# ST_Link.net
KiCad netlist of a schematic drawn in Altium Designer
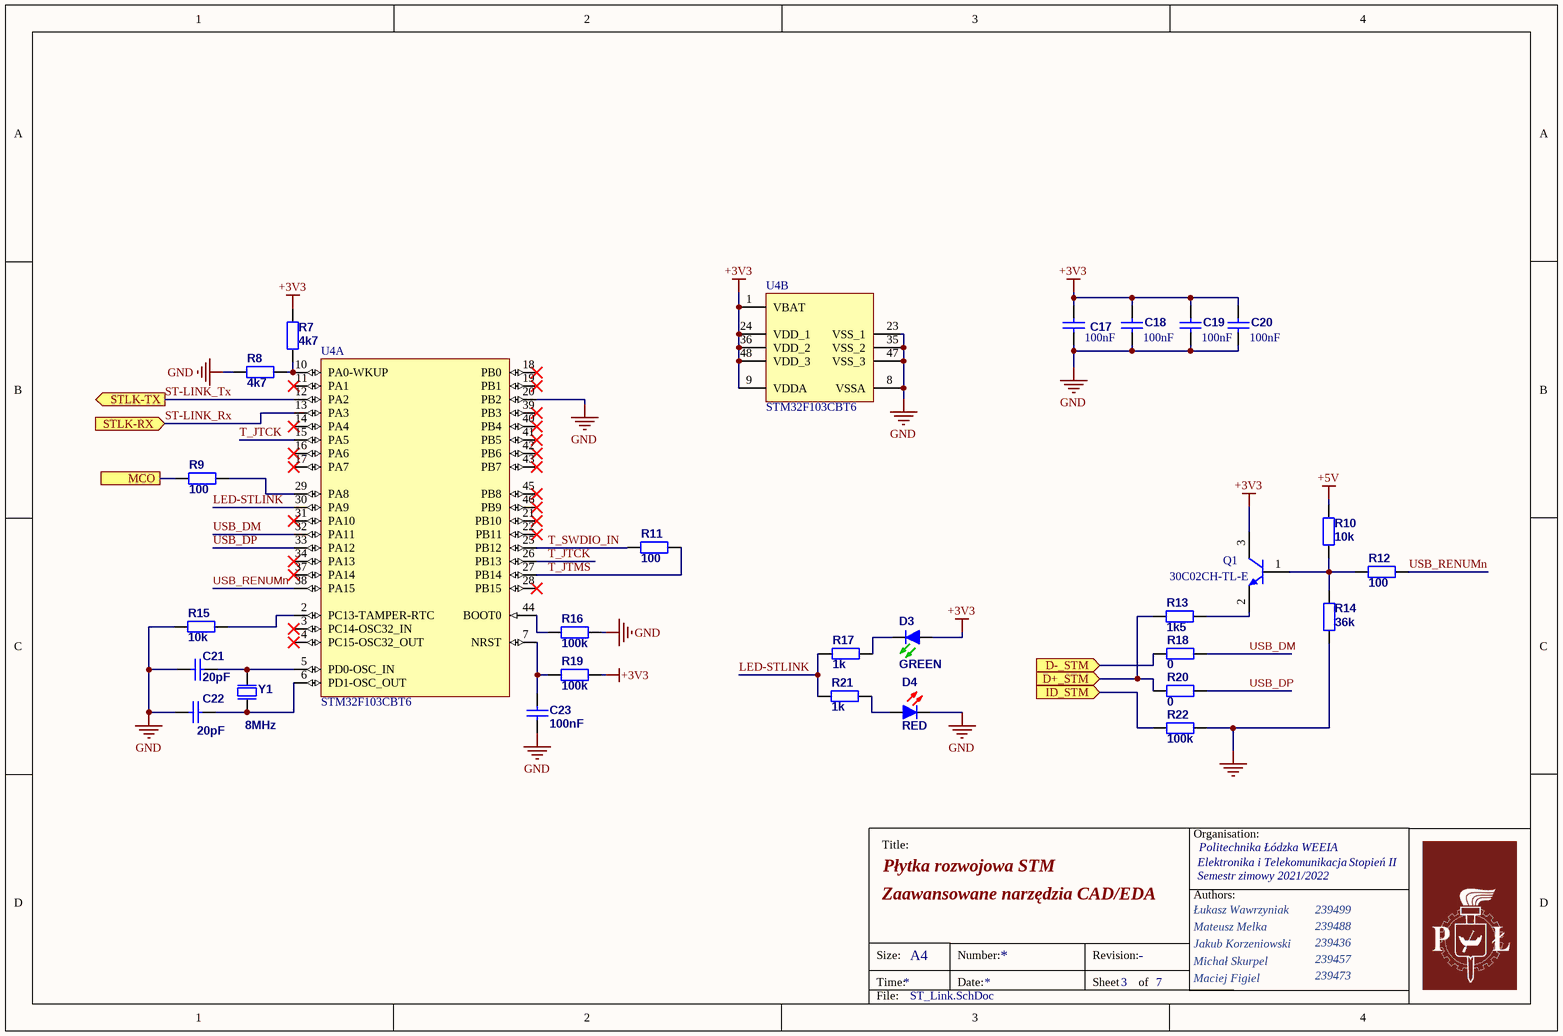
[diagram p0: ST_Link.SchDoc]

(export (version "E")
  (design (tool "Eeschema 10.0.6"))
  (components
    (comp (ref "C17")
      (value "100nF")
      (footprint "PCB1:0805")
      (description "Ceramic capacitor MLCC SMD ±1%")
      (libsource (lib "capacitors") (part "Cap"))
    )
    (comp (ref "C18")
      (value "100nF")
      (footprint "PCB1:0805")
      (description "Ceramic capacitor MLCC SMD ±1%")
      (libsource (lib "capacitors") (part "Cap"))
    )
    (comp (ref "C19")
      (value "100nF")
      (footprint "PCB1:0805")
      (description "Ceramic capacitor MLCC SMD ±1%")
      (libsource (lib "capacitors") (part "Cap"))
    )
    (comp (ref "C20")
      (value "100nF")
      (footprint "PCB1:0805")
      (description "Ceramic capacitor MLCC SMD ±1%")
      (libsource (lib "capacitors") (part "Cap"))
    )
    (comp (ref "C21")
      (value "20pF")
      (footprint "PCB1:0805")
      (description "Ceramic capacitor MLCC SMD ±1%")
      (libsource (lib "capacitors") (part "Cap"))
    )
    (comp (ref "C22")
      (value "20pF")
      (footprint "PCB1:0805")
      (description "Ceramic capacitor MLCC SMD ±1%")
      (libsource (lib "capacitors") (part "Cap"))
    )
    (comp (ref "C23")
      (value "100nF")
      (footprint "PCB1:0805")
      (description "Ceramic capacitor MLCC SMD ±5%")
      (libsource (lib "capacitors") (part "Cap"))
    )
    (comp (ref "D3")
      (value "GREEN")
      (footprint "LED1206G")
      (description "GREEN LED")
      (libsource (lib "leds") (part "LED_GREEN"))
    )
    (comp (ref "D4")
      (value "RED")
      (footprint "LED1206R")
      (description "RED LED")
      (libsource (lib "leds") (part "LED_RED"))
    )
    (comp (ref "Q1")
      (value "30C02CH-TL-E")
      (footprint "ONSC-CPH-3_V")
      (description "Bipolar Transistor,, Low VCE(sat), NPN Single, 3-Pin CPH, Pb-Free, Tape and Reel")
      (fields (field (name "MANUFACTURER") "On Semiconductor") (field (name "VOLTAGE") "30 V"))
      (libsource (lib "Altium Content Vault") (part "ONSC-30C02CH-CPH-3-318BA"))
    )
    (comp (ref "R7")
      (value "4k7")
      (footprint "PCB1:0805")
      (description "Resistor SMD  ±5%")
      (libsource (lib "resistors") (part "Res"))
    )
    (comp (ref "R8")
      (value "4k7")
      (footprint "PCB1:0805")
      (description "Resistor SMD  ±5%")
      (libsource (lib "") (part "Res_1"))
    )
    (comp (ref "R9")
      (value "100")
      (footprint "PCB1:0805")
      (description "Resistor SMD  ±5%")
      (libsource (lib "") (part "Res_1"))
    )
    (comp (ref "R10")
      (value "10k")
      (footprint "PCB1:0805")
      (description "Resistor SMD  ±5%")
      (libsource (lib "") (part "Res_2"))
    )
    (comp (ref "R11")
      (value "100")
      (footprint "PCB1:0805")
      (description "Resistor SMD  ±5%")
      (libsource (lib "") (part "Res_1"))
    )
    (comp (ref "R12")
      (value "100")
      (footprint "PCB1:0805")
      (description "Resistor SMD  ±5%")
      (libsource (lib "") (part "Res_3"))
    )
    (comp (ref "R13")
      (value "1k5")
      (footprint "PCB1:0805")
      (description "Resistor SMD  ±5%")
      (libsource (lib "") (part "Res_1"))
    )
    (comp (ref "R14")
      (value "36k")
      (footprint "PCB1:0805")
      (description "Resistor SMD  ±5%")
      (libsource (lib "resistors") (part "Res"))
    )
    (comp (ref "R15")
      (value "10k")
      (footprint "PCB1:0805")
      (description "Resistor SMD  ±5%")
      (libsource (lib "") (part "Res_1"))
    )
    (comp (ref "R16")
      (value "100k")
      (footprint "PCB1:0805")
      (description "Resistor SMD  ±5%")
      (libsource (lib "") (part "Res_1"))
    )
    (comp (ref "R17")
      (value "1k")
      (footprint "PCB1:0805")
      (description "Resistor SMD  ±5%")
      (libsource (lib "") (part "Res_1"))
    )
    (comp (ref "R18")
      (value "0")
      (footprint "PCB1:0805")
      (description "Resistor SMD  ±5%")
      (libsource (lib "") (part "Res_1"))
    )
    (comp (ref "R19")
      (value "100k")
      (footprint "PCB1:0805")
      (description "Resistor SMD  ±5%")
      (libsource (lib "") (part "Res_1"))
    )
    (comp (ref "R20")
      (value "0")
      (footprint "PCB1:0805")
      (description "Resistor SMD  ±5%")
      (libsource (lib "") (part "Res_1"))
    )
    (comp (ref "R21")
      (value "1k")
      (footprint "PCB1:0805")
      (description "Resistor SMD  ±5%")
      (libsource (lib "") (part "Res_1"))
    )
    (comp (ref "R22")
      (value "100k")
      (footprint "PCB1:0805")
      (description "Resistor SMD  ±5%")
      (libsource (lib "") (part "Res_1"))
    )
    (comp (ref "U4")
      (value "STM32F103CBT6")
      (footprint "STM-LQFP48_L")
      (fields (field (name "VOLTAGE") "3.3V"))
      (libsource (lib "Altium Content Vault") (part "MC-ARM-STM32F103X8_B-SQ48"))
    )
    (comp (ref "Y1")
      (value "8MHz")
      (footprint "HC49/4H")
      (description "Crystal Oscillator (20pF)")
      (libsource (lib "quartz_crystals_and_filters") (part "XTAL_2PIN"))
    )
  )
  (nets
    (net (code "1") (name "+3V3") (class "Default")
      (node (ref "C17") (pin "2") (pinfunction "2_2") (pintype "passive"))
      (node (ref "C18") (pin "2") (pinfunction "2_2") (pintype "passive"))
      (node (ref "C19") (pin "2") (pinfunction "2_2") (pintype "passive"))
      (node (ref "C20") (pin "2") (pinfunction "2_2") (pintype "passive"))
      (node (ref "D3") (pin "1") (pinfunction "A_1") (pintype "passive"))
      (node (ref "Q1") (pin "3") (pinfunction "C_3") (pintype "passive"))
      (node (ref "R19") (pin "1") (pinfunction "1_1") (pintype "passive"))
      (node (ref "R7") (pin "1") (pinfunction "1_1") (pintype "passive"))
      (node (ref "U4") (pin "1") (pinfunction "VBAT_1") (pintype "power_in"))
      (node (ref "U4") (pin "24") (pinfunction "VDD_1_24") (pintype "power_in"))
      (node (ref "U4") (pin "36") (pinfunction "VDD_2_36") (pintype "power_in"))
      (node (ref "U4") (pin "48") (pinfunction "VDD_3_48") (pintype "power_in"))
      (node (ref "U4") (pin "9") (pinfunction "VDDA_9") (pintype "power_in"))
    )
    (net (code "2") (name "+5V") (class "Default")
      (node (ref "R10") (pin "2") (pinfunction "2_2") (pintype "passive"))
    )
    (net (code "3") (name "/D+_STM") (class "Default")
      (node (ref "R13") (pin "2") (pinfunction "2_2") (pintype "passive"))
      (node (ref "R20") (pin "2") (pinfunction "2_2") (pintype "passive"))
    )
    (net (code "4") (name "/D-_STM") (class "Default")
      (node (ref "R18") (pin "2") (pinfunction "2_2") (pintype "passive"))
    )
    (net (code "5") (name "/ID_STM") (class "Default")
      (node (ref "R22") (pin "2") (pinfunction "2_2") (pintype "passive"))
    )
    (net (code "6") (name "/LED-STLINK") (class "Default")
      (node (ref "R17") (pin "2") (pinfunction "2_2") (pintype "passive"))
      (node (ref "R21") (pin "2") (pinfunction "2_2") (pintype "passive"))
      (node (ref "U4") (pin "30") (pinfunction "PA9_30") (pintype "bidirectional"))
    )
    (net (code "7") (name "/MCO") (class "Default")
      (node (ref "R9") (pin "2") (pinfunction "2_2") (pintype "passive"))
    )
    (net (code "8") (name "/ST-LINK_Rx") (class "Default")
      (node (ref "U4") (pin "13") (pinfunction "PA3_13") (pintype "bidirectional"))
    )
    (net (code "9") (name "/ST-LINK_Tx") (class "Default")
      (node (ref "U4") (pin "12") (pinfunction "PA2_12") (pintype "bidirectional"))
    )
    (net (code "10") (name "/T_JTCK") (class "Default")
      (node (ref "U4") (pin "15") (pinfunction "PA5_15") (pintype "bidirectional"))
      (node (ref "U4") (pin "26") (pinfunction "PB13_26") (pintype "bidirectional"))
    )
    (net (code "11") (name "/T_JTMS") (class "Default")
      (node (ref "R11") (pin "1") (pinfunction "1_1") (pintype "passive"))
      (node (ref "U4") (pin "27") (pinfunction "PB14_27") (pintype "bidirectional"))
    )
    (net (code "12") (name "/T_SWDIO_IN") (class "Default")
      (node (ref "R11") (pin "2") (pinfunction "2_2") (pintype "passive"))
      (node (ref "U4") (pin "25") (pinfunction "PB12_25") (pintype "bidirectional"))
    )
    (net (code "13") (name "/USB_DM") (class "Default")
      (node (ref "R18") (pin "1") (pinfunction "1_1") (pintype "passive"))
      (node (ref "U4") (pin "32") (pinfunction "PA11_32") (pintype "bidirectional"))
    )
    (net (code "14") (name "/USB_DP") (class "Default")
      (node (ref "R20") (pin "1") (pinfunction "1_1") (pintype "passive"))
      (node (ref "U4") (pin "33") (pinfunction "PA12_33") (pintype "bidirectional"))
    )
    (net (code "15") (name "/USB_RENUMn") (class "Default")
      (node (ref "R12") (pin "2") (pinfunction "2_2") (pintype "passive"))
      (node (ref "U4") (pin "38") (pinfunction "PA15_38") (pintype "bidirectional"))
    )
    (net (code "16") (name "GND") (class "Default")
      (node (ref "C17") (pin "1") (pinfunction "1_1") (pintype "passive"))
      (node (ref "C18") (pin "1") (pinfunction "1_1") (pintype "passive"))
      (node (ref "C19") (pin "1") (pinfunction "1_1") (pintype "passive"))
      (node (ref "C20") (pin "1") (pinfunction "1_1") (pintype "passive"))
      (node (ref "C21") (pin "1") (pinfunction "1_1") (pintype "passive"))
      (node (ref "C22") (pin "1") (pinfunction "1_1") (pintype "passive"))
      (node (ref "C23") (pin "1") (pinfunction "1_1") (pintype "passive"))
      (node (ref "D4") (pin "2") (pinfunction "K_2") (pintype "passive"))
      (node (ref "R14") (pin "2") (pinfunction "2_2") (pintype "passive"))
      (node (ref "R15") (pin "2") (pinfunction "2_2") (pintype "passive"))
      (node (ref "R16") (pin "1") (pinfunction "1_1") (pintype "passive"))
      (node (ref "R22") (pin "1") (pinfunction "1_1") (pintype "passive"))
      (node (ref "R8") (pin "2") (pinfunction "2_2") (pintype "passive"))
      (node (ref "U4") (pin "20") (pinfunction "PB2_20") (pintype "bidirectional"))
      (node (ref "U4") (pin "23") (pinfunction "VSS_1_23") (pintype "power_in"))
      (node (ref "U4") (pin "35") (pinfunction "VSS_2_35") (pintype "power_in"))
      (node (ref "U4") (pin "47") (pinfunction "VSS_3_47") (pintype "power_in"))
      (node (ref "U4") (pin "8") (pinfunction "VSSA_8") (pintype "power_in"))
    )
    (net (code "17") (name "Net-(D3-K)") (class "Default")
      (node (ref "D3") (pin "2") (pinfunction "K_2") (pintype "passive"))
      (node (ref "R17") (pin "1") (pinfunction "1_1") (pintype "passive"))
    )
    (net (code "18") (name "Net-(D4-A)") (class "Default")
      (node (ref "D4") (pin "1") (pinfunction "A_1") (pintype "passive"))
      (node (ref "R21") (pin "1") (pinfunction "1_1") (pintype "passive"))
    )
    (net (code "19") (name "Net-(Q1-B)") (class "Default")
      (node (ref "Q1") (pin "1") (pinfunction "B_1") (pintype "passive"))
      (node (ref "R10") (pin "1") (pinfunction "1_1") (pintype "passive"))
      (node (ref "R12") (pin "1") (pinfunction "1_1") (pintype "passive"))
      (node (ref "R14") (pin "1") (pinfunction "1_1") (pintype "passive"))
    )
    (net (code "20") (name "Net-(Q1-E)") (class "Default")
      (node (ref "Q1") (pin "2") (pinfunction "E_2") (pintype "passive"))
      (node (ref "R13") (pin "1") (pinfunction "1_1") (pintype "passive"))
    )
    (net (code "21") (name "Net-(U4A-BOOT0)") (class "Default")
      (node (ref "R16") (pin "2") (pinfunction "2_2") (pintype "passive"))
      (node (ref "U4") (pin "44") (pinfunction "BOOT0_44") (pintype "input"))
    )
    (net (code "22") (name "Net-(U4A-NRST)") (class "Default")
      (node (ref "C23") (pin "2") (pinfunction "2_2") (pintype "passive"))
      (node (ref "R19") (pin "2") (pinfunction "2_2") (pintype "passive"))
      (node (ref "U4") (pin "7") (pinfunction "NRST_7") (pintype "bidirectional"))
    )
    (net (code "23") (name "Net-(U4A-PA0-WKUP)") (class "Default")
      (node (ref "R7") (pin "2") (pinfunction "2_2") (pintype "passive"))
      (node (ref "R8") (pin "1") (pinfunction "1_1") (pintype "passive"))
      (node (ref "U4") (pin "10") (pinfunction "PA0-WKUP_10") (pintype "bidirectional"))
    )
    (net (code "24") (name "Net-(U4A-PA8)") (class "Default")
      (node (ref "R9") (pin "1") (pinfunction "1_1") (pintype "passive"))
      (node (ref "U4") (pin "29") (pinfunction "PA8_29") (pintype "bidirectional"))
    )
    (net (code "25") (name "Net-(U4A-PC13-TAMPER-RTC)") (class "Default")
      (node (ref "R15") (pin "1") (pinfunction "1_1") (pintype "passive"))
      (node (ref "U4") (pin "2") (pinfunction "PC13-TAMPER-RTC_2") (pintype "bidirectional"))
    )
    (net (code "26") (name "Net-(U4A-PD0-OSC_IN)") (class "Default")
      (node (ref "C21") (pin "2") (pinfunction "2_2") (pintype "passive"))
      (node (ref "U4") (pin "5") (pinfunction "PD0-OSC_IN_5") (pintype "bidirectional"))
      (node (ref "Y1") (pin "2") (pinfunction "OSC2_2") (pintype "passive"))
    )
    (net (code "27") (name "Net-(U4A-PD1-OSC_OUT)") (class "Default")
      (node (ref "C22") (pin "2") (pinfunction "2_2") (pintype "passive"))
      (node (ref "U4") (pin "6") (pinfunction "PD1-OSC_OUT_6") (pintype "bidirectional"))
      (node (ref "Y1") (pin "1") (pinfunction "OSC1_1") (pintype "passive"))
    )
    (net (code "28") (name "unconnected-(U4A-PA1-Pad11)") (class "Default")
      (node (ref "U4") (pin "11") (pinfunction "PA1_11") (pintype "bidirectional+no_connect"))
    )
    (net (code "29") (name "unconnected-(U4A-PA4-Pad14)") (class "Default")
      (node (ref "U4") (pin "14") (pinfunction "PA4_14") (pintype "bidirectional+no_connect"))
    )
    (net (code "30") (name "unconnected-(U4A-PA6-Pad16)") (class "Default")
      (node (ref "U4") (pin "16") (pinfunction "PA6_16") (pintype "bidirectional+no_connect"))
    )
    (net (code "31") (name "unconnected-(U4A-PA7-Pad17)") (class "Default")
      (node (ref "U4") (pin "17") (pinfunction "PA7_17") (pintype "bidirectional+no_connect"))
    )
    (net (code "32") (name "unconnected-(U4A-PA10-Pad31)") (class "Default")
      (node (ref "U4") (pin "31") (pinfunction "PA10_31") (pintype "bidirectional+no_connect"))
    )
    (net (code "33") (name "unconnected-(U4A-PA13-Pad34)") (class "Default")
      (node (ref "U4") (pin "34") (pinfunction "PA13_34") (pintype "bidirectional+no_connect"))
    )
    (net (code "34") (name "unconnected-(U4A-PA14-Pad37)") (class "Default")
      (node (ref "U4") (pin "37") (pinfunction "PA14_37") (pintype "bidirectional+no_connect"))
    )
    (net (code "35") (name "unconnected-(U4A-PB0-Pad18)") (class "Default")
      (node (ref "U4") (pin "18") (pinfunction "PB0_18") (pintype "bidirectional+no_connect"))
    )
    (net (code "36") (name "unconnected-(U4A-PB1-Pad19)") (class "Default")
      (node (ref "U4") (pin "19") (pinfunction "PB1_19") (pintype "bidirectional+no_connect"))
    )
    (net (code "37") (name "unconnected-(U4A-PB3-Pad39)") (class "Default")
      (node (ref "U4") (pin "39") (pinfunction "PB3_39") (pintype "bidirectional+no_connect"))
    )
    (net (code "38") (name "unconnected-(U4A-PB4-Pad40)") (class "Default")
      (node (ref "U4") (pin "40") (pinfunction "PB4_40") (pintype "bidirectional+no_connect"))
    )
    (net (code "39") (name "unconnected-(U4A-PB5-Pad41)") (class "Default")
      (node (ref "U4") (pin "41") (pinfunction "PB5_41") (pintype "bidirectional+no_connect"))
    )
    (net (code "40") (name "unconnected-(U4A-PB6-Pad42)") (class "Default")
      (node (ref "U4") (pin "42") (pinfunction "PB6_42") (pintype "bidirectional+no_connect"))
    )
    (net (code "41") (name "unconnected-(U4A-PB7-Pad43)") (class "Default")
      (node (ref "U4") (pin "43") (pinfunction "PB7_43") (pintype "bidirectional+no_connect"))
    )
    (net (code "42") (name "unconnected-(U4A-PB8-Pad45)") (class "Default")
      (node (ref "U4") (pin "45") (pinfunction "PB8_45") (pintype "bidirectional+no_connect"))
    )
    (net (code "43") (name "unconnected-(U4A-PB9-Pad46)") (class "Default")
      (node (ref "U4") (pin "46") (pinfunction "PB9_46") (pintype "bidirectional+no_connect"))
    )
    (net (code "44") (name "unconnected-(U4A-PB10-Pad21)") (class "Default")
      (node (ref "U4") (pin "21") (pinfunction "PB10_21") (pintype "bidirectional+no_connect"))
    )
    (net (code "45") (name "unconnected-(U4A-PB11-Pad22)") (class "Default")
      (node (ref "U4") (pin "22") (pinfunction "PB11_22") (pintype "bidirectional+no_connect"))
    )
    (net (code "46") (name "unconnected-(U4A-PB15-Pad28)") (class "Default")
      (node (ref "U4") (pin "28") (pinfunction "PB15_28") (pintype "bidirectional+no_connect"))
    )
    (net (code "47") (name "unconnected-(U4A-PC14-OSC32_IN-Pad3)") (class "Default")
      (node (ref "U4") (pin "3") (pinfunction "PC14-OSC32_IN_3") (pintype "bidirectional+no_connect"))
    )
    (net (code "48") (name "unconnected-(U4A-PC15-OSC32_OUT-Pad4)") (class "Default")
      (node (ref "U4") (pin "4") (pinfunction "PC15-OSC32_OUT_4") (pintype "bidirectional+no_connect"))
    )
  )
)
